# Weatstone_Bridge_Design.net
KiCad netlist of a schematic drawn in Altium Designer
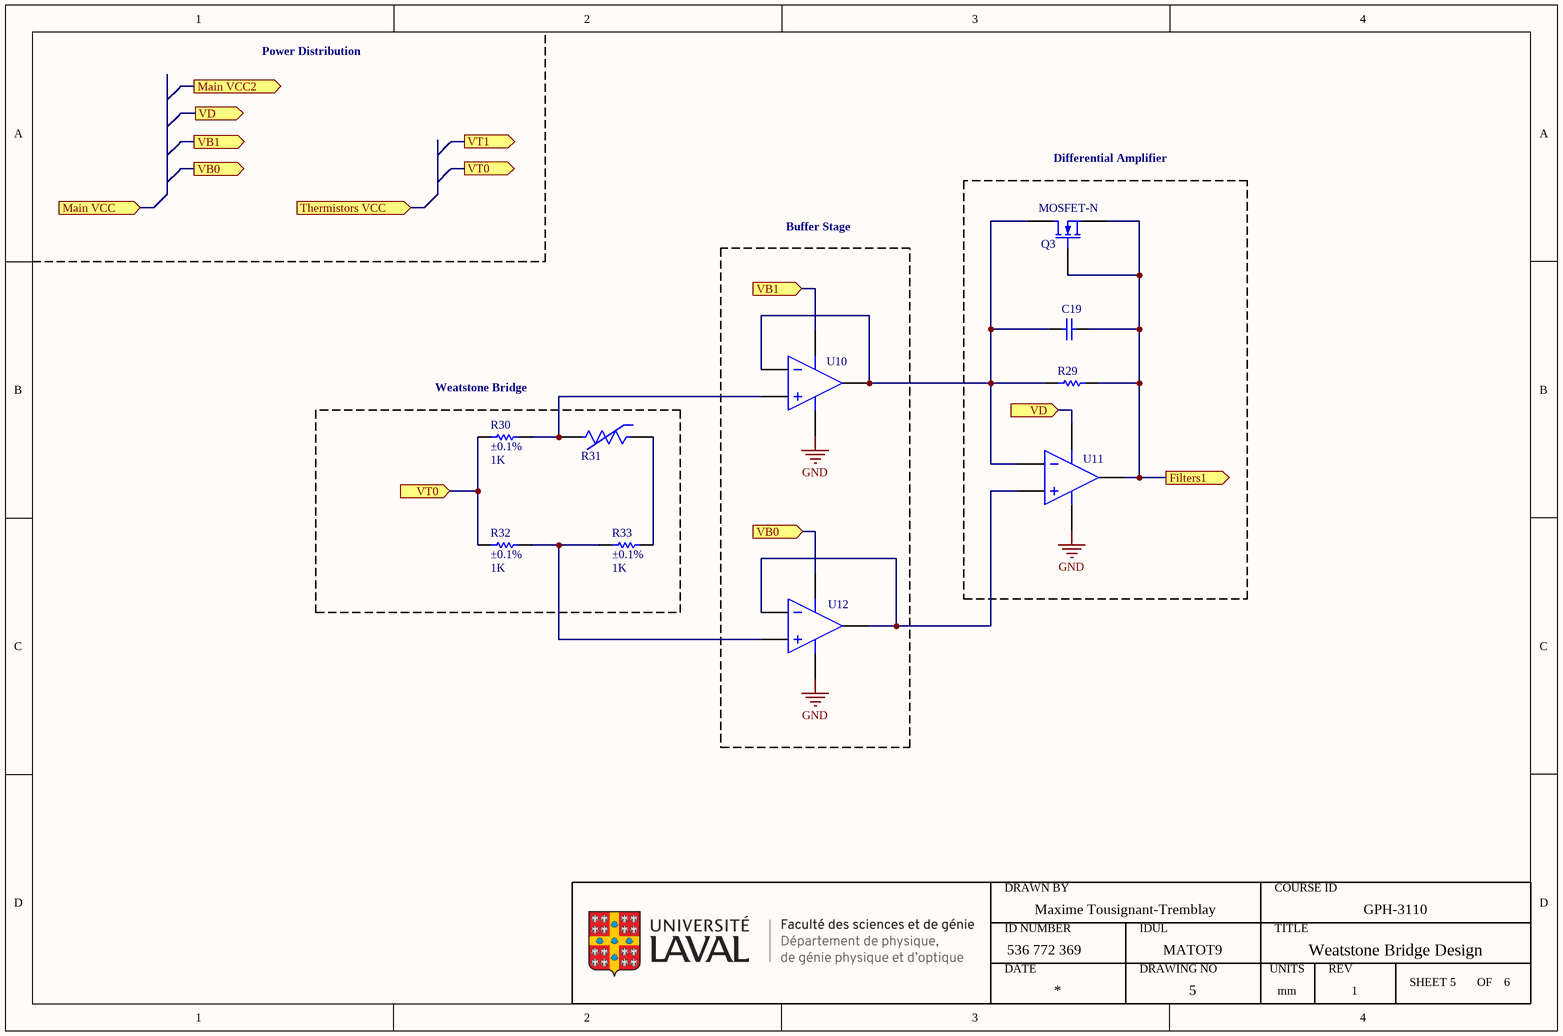
[diagram p0: Weatstone Bridge Design.SchDoc]

(export (version "E")
  (design (tool "Eeschema 10.0.6"))
  (components
    (comp (ref "*5")
      (value "ULaval FSG-DPGPO")
      (libsource (lib "ULaval Title Block") (part "ULaval FSG-DPGPO"))
    )
    (comp (ref "C19")
      (value "Capacitor")
      (libsource (lib "Simulation Generic Components") (part "Capacitor"))
    )
    (comp (ref "Q3")
      (value "MOSFET-N")
      (footprint "E3")
      (description "N-Channel MOSFET")
      (fields (field (name "PUBLISHER") "Altium Limited"))
      (libsource (lib "Miscellaneous Devices") (part "MOSFET-N"))
    )
    (comp (ref "R29") (value "Resistor") (libsource (lib "Simulation Generic Components") (part "Resistor")))
    (comp (ref "R30")
      (value "1K")
      (description "Resistor")
      (fields (field (name "TC") "±0.1%"))
      (libsource (lib "Simulation Generic Components") (part "Resistor"))
    )
    (comp (ref "R31")
      (value "TMP6131DYAT")
      (footprint "FP-DYA0002A-MFG")
      (libsource (lib "Laval University") (part "d90f1a9d369475ff918e5c0a1e42652"))
    )
    (comp (ref "R32")
      (value "1K")
      (description "Resistor")
      (fields (field (name "TC") "±0.1%"))
      (libsource (lib "Simulation Generic Components") (part "Resistor"))
    )
    (comp (ref "R33")
      (value "1K")
      (description "Resistor")
      (fields (field (name "TC") "±0.1%"))
      (libsource (lib "Simulation Generic Components") (part "Resistor"))
    )
    (comp (ref "U10")
      (value "Ideal Operational Amplifier")
      (libsource (lib "Simulation Generic Components") (part "OpAmp with power terminals"))
    )
    (comp (ref "U11")
      (value "Ideal Operational Amplifier")
      (libsource (lib "Simulation Generic Components") (part "OpAmp with power terminals"))
    )
    (comp (ref "U12")
      (value "Ideal Operational Amplifier")
      (libsource (lib "Simulation Generic Components") (part "OpAmp with power terminals"))
    )
  )
  (nets
    (net (code "1") (name "/Filters1") (class "Default")
      (node (ref "C19") (pin "2") (pinfunction "2_2") (pintype "passive"))
      (node (ref "Q3") (pin "2") (pinfunction "G_2") (pintype "passive"))
      (node (ref "Q3") (pin "3") (pinfunction "S_3") (pintype "passive"))
      (node (ref "R29") (pin "2") (pinfunction "2_2") (pintype "passive"))
      (node (ref "U11") (pin "3") (pinfunction "OUT_3") (pintype "passive"))
    )
    (net (code "5") (name "/VB0") (class "Default")
      (node (ref "U12") (pin "4") (pinfunction "V+_4") (pintype "power_in"))
    )
    (net (code "6") (name "/VB1") (class "Default")
      (node (ref "U10") (pin "4") (pinfunction "V+_4") (pintype "power_in"))
    )
    (net (code "7") (name "/VD") (class "Default")
      (node (ref "U11") (pin "4") (pinfunction "V+_4") (pintype "power_in"))
    )
    (net (code "8") (name "/VT0") (class "Default")
      (node (ref "R30") (pin "2") (pinfunction "2_2") (pintype "passive"))
      (node (ref "R32") (pin "2") (pinfunction "2_2") (pintype "passive"))
    )
    (net (code "10") (name "GND") (class "Default")
      (node (ref "U10") (pin "5") (pinfunction "V-_5") (pintype "power_in"))
      (node (ref "U11") (pin "5") (pinfunction "V-_5") (pintype "power_in"))
      (node (ref "U12") (pin "5") (pinfunction "V-_5") (pintype "power_in"))
    )
    (net (code "11") (name "Net-(Q3-D)") (class "Default")
      (node (ref "C19") (pin "1") (pinfunction "1_1") (pintype "passive"))
      (node (ref "Q3") (pin "1") (pinfunction "D_1") (pintype "passive"))
    )
    (net (code "12") (name "Net-(R31-+)") (class "Default")
      (node (ref "R31") (pin "2") (pinfunction "+_2") (pintype "passive"))
      (node (ref "R33") (pin "1") (pinfunction "1_1") (pintype "passive"))
    )
    (net (code "13") (name "Net-(R31--)") (class "Default")
      (node (ref "R30") (pin "1") (pinfunction "1_1") (pintype "passive"))
      (node (ref "R31") (pin "1") (pinfunction "-_1") (pintype "passive"))
      (node (ref "U10") (pin "2") (pinfunction "IN+_2") (pintype "passive"))
    )
    (net (code "14") (name "Net-(U10-IN-)") (class "Default")
      (node (ref "R29") (pin "1") (pinfunction "1_1") (pintype "passive"))
      (node (ref "U10") (pin "1") (pinfunction "IN-_1") (pintype "passive"))
      (node (ref "U10") (pin "3") (pinfunction "OUT_3") (pintype "passive"))
      (node (ref "U11") (pin "1") (pinfunction "IN-_1") (pintype "passive"))
    )
    (net (code "15") (name "Net-(U11-IN+)") (class "Default")
      (node (ref "U11") (pin "2") (pinfunction "IN+_2") (pintype "passive"))
      (node (ref "U12") (pin "1") (pinfunction "IN-_1") (pintype "passive"))
      (node (ref "U12") (pin "3") (pinfunction "OUT_3") (pintype "passive"))
    )
    (net (code "16") (name "Net-(U12-IN+)") (class "Default")
      (node (ref "R32") (pin "1") (pinfunction "1_1") (pintype "passive"))
      (node (ref "R33") (pin "2") (pinfunction "2_2") (pintype "passive"))
      (node (ref "U12") (pin "2") (pinfunction "IN+_2") (pintype "passive"))
    )
  )
)
